# connectors.net
KiCad netlist of a schematic drawn in Altium Designer
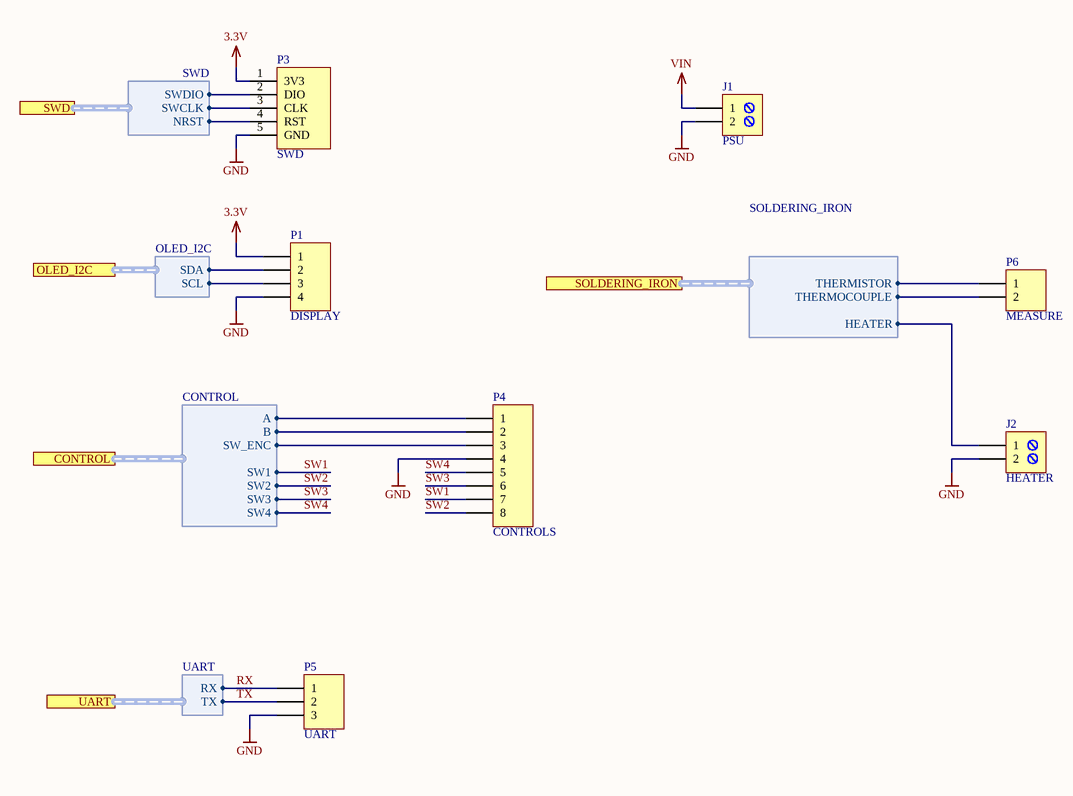
[diagram p0: connectors.SchDoc]

(export (version "E")
  (design (tool "Eeschema 10.0.6"))
  (components
    (comp (ref "J1")
      (value "PSU")
      (footprint "J_ARK2")
      (description "ARK Screw terminal, 2-Pin")
      (fields (field (name "PART NUMBER") "J_TB-5.0-P-2P") (field (name "MANUFACTURER") "DEGSON ELECTRONICS"))
      (libsource (lib "Library") (part "J_ARK2"))
    )
    (comp (ref "J2")
      (value "HEATER")
      (footprint "J_ARK2")
      (description "ARK Screw terminal, 2-Pin")
      (fields (field (name "PART NUMBER") "J_TB-5.0-P-2P") (field (name "MANUFACTURER") "DEGSON ELECTRONICS"))
      (libsource (lib "Library") (part "J_ARK2"))
    )
    (comp (ref "P1")
      (value "DISPLAY")
      (footprint "P_HEADER_1x4_2.54")
      (description "Header, 4-Pin")
      (fields (field (name "PART NUMBER") "P_HEADER_1x4_2.54") (field (name "MANUFACTURER") "Connfly"))
      (libsource (lib "Library") (part "P_HEADER_1x4"))
    )
    (comp (ref "P3")
      (value "SWD")
      (footprint "SWD_Header")
      (description "1x5 2.54 SWD Header")
      (libsource (lib "soldering_station") (part "SWD_Header"))
    )
    (comp (ref "P4")
      (value "CONTROLS")
      (footprint "P_HEADER_1x8_2.54")
      (description "Header, 8-Pin")
      (fields (field (name "PART NUMBER") "P_HEADER_1x8_2.54") (field (name "MANUFACTURER") "Connfly"))
      (libsource (lib "Library") (part "P_HEADER_1x8"))
    )
    (comp (ref "P5")
      (value "UART")
      (footprint "P_HEADER_1x3_2.54")
      (description "Header, 3-Pin")
      (fields (field (name "PART NUMBER") "P_HEADER_1x3_2.54") (field (name "MANUFACTURER") "Connfly"))
      (libsource (lib "Library") (part "P_HEADER_1x3"))
    )
    (comp (ref "P6")
      (value "MEASURE")
      (footprint "P_HEADER_1x2_2.54")
      (description "Header, 2-Pin")
      (fields (field (name "PART NUMBER") "P_HEADER_1x2_2.54") (field (name "MANUFACTURER") "Connfly"))
      (libsource (lib "Library") (part "P_HEADER_1x2"))
    )
  )
  (nets
    (net (code "6") (name "/A") (class "Default")
      (node (ref "P4") (pin "1") (pinfunction "1_1") (pintype "passive"))
    )
    (net (code "7") (name "/B") (class "Default")
      (node (ref "P4") (pin "2") (pinfunction "2_2") (pintype "passive"))
    )
    (net (code "8") (name "/HEATER") (class "Default")
      (node (ref "J2") (pin "1") (pinfunction "1_1") (pintype "passive"))
    )
    (net (code "9") (name "/NRST") (class "Default")
      (node (ref "P3") (pin "4") (pinfunction "RST_4") (pintype "passive"))
    )
    (net (code "10") (name "/RX") (class "Default")
      (node (ref "P5") (pin "1") (pinfunction "1_1") (pintype "passive"))
    )
    (net (code "11") (name "/SCL") (class "Default")
      (node (ref "P1") (pin "3") (pinfunction "3_3") (pintype "passive"))
    )
    (net (code "12") (name "/SDA") (class "Default")
      (node (ref "P1") (pin "2") (pinfunction "2_2") (pintype "passive"))
    )
    (net (code "13") (name "/SW1") (class "Default")
      (node (ref "P4") (pin "7") (pinfunction "7_7") (pintype "passive"))
    )
    (net (code "14") (name "/SW2") (class "Default")
      (node (ref "P4") (pin "8") (pinfunction "8_8") (pintype "passive"))
    )
    (net (code "15") (name "/SW3") (class "Default")
      (node (ref "P4") (pin "6") (pinfunction "6_6") (pintype "passive"))
    )
    (net (code "16") (name "/SW4") (class "Default")
      (node (ref "P4") (pin "5") (pinfunction "5_5") (pintype "passive"))
    )
    (net (code "17") (name "/SWCLK") (class "Default")
      (node (ref "P3") (pin "3") (pinfunction "CLK_3") (pintype "passive"))
    )
    (net (code "18") (name "/SWDIO") (class "Default")
      (node (ref "P3") (pin "2") (pinfunction "DIO_2") (pintype "passive"))
    )
    (net (code "19") (name "/SW_ENC") (class "Default")
      (node (ref "P4") (pin "3") (pinfunction "3_3") (pintype "passive"))
    )
    (net (code "20") (name "/THERMISTOR") (class "Default")
      (node (ref "P6") (pin "1") (pinfunction "1_1") (pintype "passive"))
    )
    (net (code "21") (name "/THERMOCOUPLE") (class "Default")
      (node (ref "P6") (pin "2") (pinfunction "2_2") (pintype "passive"))
    )
    (net (code "22") (name "/TX") (class "Default")
      (node (ref "P5") (pin "2") (pinfunction "2_2") (pintype "passive"))
    )
    (net (code "28") (name "3.3V") (class "Default")
      (node (ref "P1") (pin "1") (pinfunction "1_1") (pintype "passive"))
      (node (ref "P3") (pin "1") (pinfunction "3V3_1") (pintype "passive"))
    )
    (net (code "29") (name "GND") (class "Default")
      (node (ref "J1") (pin "2") (pinfunction "2_2") (pintype "passive"))
      (node (ref "J2") (pin "2") (pinfunction "2_2") (pintype "passive"))
      (node (ref "P1") (pin "4") (pinfunction "4_4") (pintype "passive"))
      (node (ref "P3") (pin "5") (pinfunction "GND_5") (pintype "passive"))
      (node (ref "P4") (pin "4") (pinfunction "4_4") (pintype "passive"))
      (node (ref "P5") (pin "3") (pinfunction "3_3") (pintype "passive"))
    )
    (net (code "30") (name "VIN") (class "Default")
      (node (ref "J1") (pin "1") (pinfunction "1_1") (pintype "passive"))
    )
  )
)
